# SxC_MuxJTAG.net
KiCad netlist of a schematic drawn in Altium Designer
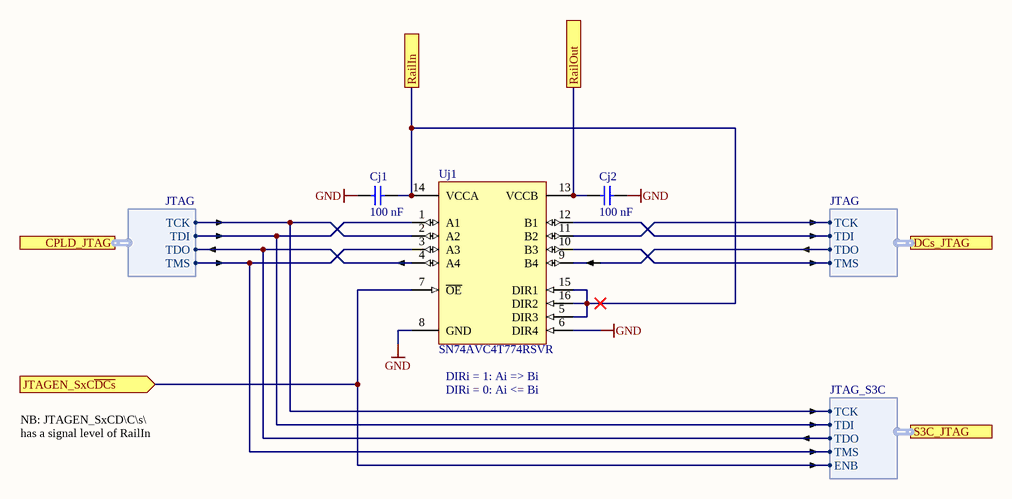
[diagram p0: SxC_MuxJTAG.SchDoc]

(export (version "E")
  (design (tool "Eeschema 10.0.6"))
  (components
    (comp (ref "Cj1")
      (value "100 nF")
      (footprint "C_0603_TE")
      (description "Generic capacitor")
      (fields
        (field (name "TOLERANCE") "10 %")
        (field (name "VOLTAGE") "50 V")
        (field (name "CREATED FROM") "AGeiger")
      )
      (libsource (lib "user") (part "CAP-NP"))
    )
    (comp (ref "Cj2")
      (value "100 nF")
      (footprint "C_0603_TE")
      (description "Generic capacitor")
      (fields
        (field (name "TOLERANCE") "10 %")
        (field (name "VOLTAGE") "50 V")
        (field (name "CREATED FROM") "AGeiger")
      )
      (libsource (lib "user") (part "CAP-NP"))
    )
    (comp (ref "Uj1")
      (value "SN74AVC4T774RSVR")
      (footprint "QFN40P260X180X55-16N")
      (fields
        (field (name "MANUFACTURER") "Texas Instruments")
        (field (name "LCSC PART NUMBER") "C779392")
        (field (name "CREATED FROM") "MGremer")
      )
      (libsource (lib "user") (part "SN74AVC4T774RSVR"))
    )
  )
  (nets
    (net (code "3") (name "/JTAGEN_SxC~{DCs}") (class "Default")
      (node (ref "Uj1") (pin "7") (pinfunction "~{OE}_7") (pintype "input"))
    )
    (net (code "4") (name "/RailIn") (class "Default")
      (node (ref "Cj1") (pin "1") (pinfunction "1_1") (pintype "passive"))
      (node (ref "Uj1") (pin "14") (pinfunction "VCCA_14") (pintype "power_in"))
      (node (ref "Uj1") (pin "15") (pinfunction "DIR1_15") (pintype "input"))
      (node (ref "Uj1") (pin "16") (pinfunction "DIR2_16") (pintype "input"))
      (node (ref "Uj1") (pin "5") (pinfunction "DIR3_5") (pintype "input"))
    )
    (net (code "5") (name "/RailOut") (class "Default")
      (node (ref "Cj2") (pin "2") (pinfunction "2_2") (pintype "passive"))
      (node (ref "Uj1") (pin "13") (pinfunction "VCCB_13") (pintype "power_in"))
    )
    (net (code "8") (name "GND") (class "Default")
      (node (ref "Cj1") (pin "2") (pinfunction "2_2") (pintype "passive"))
      (node (ref "Cj2") (pin "1") (pinfunction "1_1") (pintype "passive"))
      (node (ref "Uj1") (pin "6") (pinfunction "DIR4_6") (pintype "input"))
      (node (ref "Uj1") (pin "8") (pinfunction "GND_8") (pintype "power_in"))
    )
    (net (code "9") (name "unconnected-(Uj1-A1-Pad1)") (class "Default")
      (node (ref "Uj1") (pin "1") (pinfunction "A1_1") (pintype "bidirectional"))
    )
    (net (code "10") (name "unconnected-(Uj1-A2-Pad2)") (class "Default")
      (node (ref "Uj1") (pin "2") (pinfunction "A2_2") (pintype "bidirectional"))
    )
    (net (code "11") (name "unconnected-(Uj1-A3-Pad3)") (class "Default")
      (node (ref "Uj1") (pin "3") (pinfunction "A3_3") (pintype "bidirectional"))
    )
    (net (code "12") (name "unconnected-(Uj1-A4-Pad4)") (class "Default")
      (node (ref "Uj1") (pin "4") (pinfunction "A4_4") (pintype "bidirectional"))
    )
    (net (code "13") (name "unconnected-(Uj1-B1-Pad12)") (class "Default")
      (node (ref "Uj1") (pin "12") (pinfunction "B1_12") (pintype "bidirectional"))
    )
    (net (code "14") (name "unconnected-(Uj1-B2-Pad11)") (class "Default")
      (node (ref "Uj1") (pin "11") (pinfunction "B2_11") (pintype "bidirectional"))
    )
    (net (code "15") (name "unconnected-(Uj1-B3-Pad10)") (class "Default")
      (node (ref "Uj1") (pin "10") (pinfunction "B3_10") (pintype "bidirectional"))
    )
    (net (code "16") (name "unconnected-(Uj1-B4-Pad9)") (class "Default")
      (node (ref "Uj1") (pin "9") (pinfunction "B4_9") (pintype "bidirectional"))
    )
  )
)
